# input5.net
KiCad netlist of a schematic drawn in Altium Designer
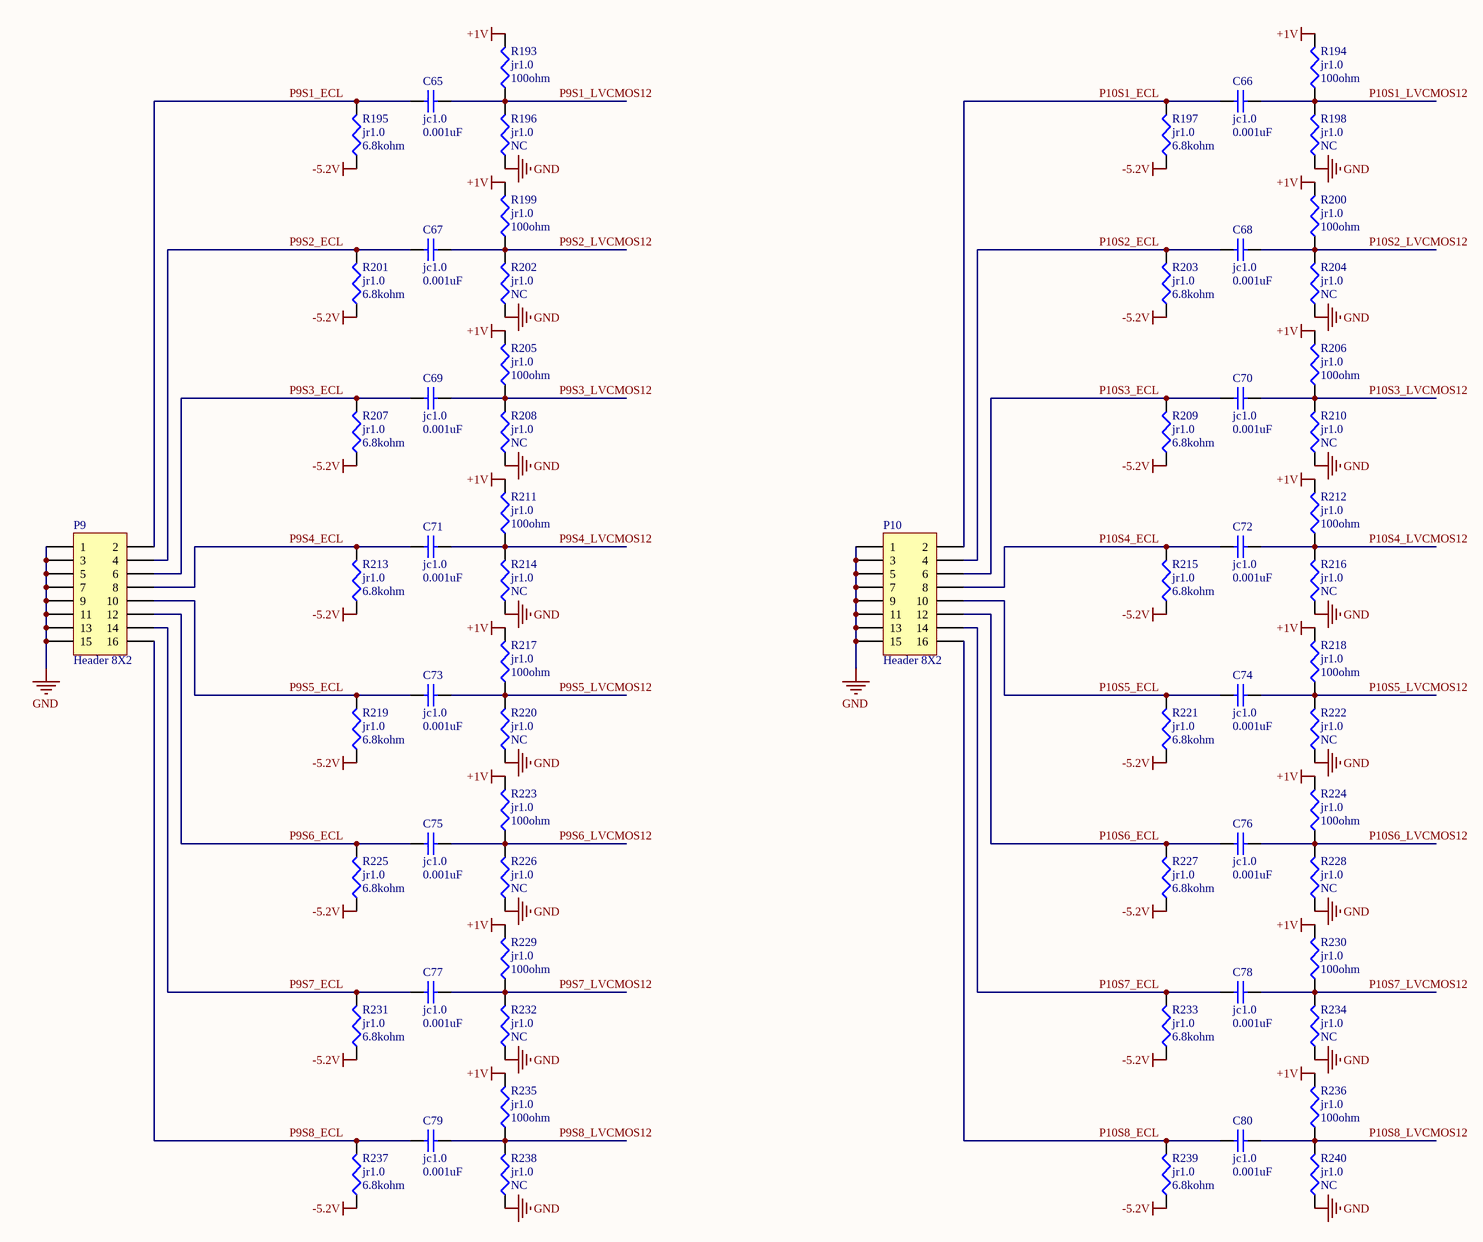
[diagram p0: input5.SchDoc]

(export (version "E")
  (design (tool "Eeschema 10.0.6"))
  (components
    (comp (ref "C65")
      (value "jc1.0")
      (footprint "0402")
      (description "Capacitor")
      (fields (field (name "ALTIUM_VALUE") "0.001uF") (field (name "PUBLISHER") "Altium Limited"))
      (libsource (lib "LIB01DXP2006SchLib") (part "Cap"))
    )
    (comp (ref "C66")
      (value "jc1.0")
      (footprint "0402")
      (description "Capacitor")
      (fields (field (name "ALTIUM_VALUE") "0.001uF") (field (name "PUBLISHER") "Altium Limited"))
      (libsource (lib "LIB01DXP2006SchLib") (part "Cap"))
    )
    (comp (ref "C67")
      (value "jc1.0")
      (footprint "0402")
      (description "Capacitor")
      (fields (field (name "ALTIUM_VALUE") "0.001uF") (field (name "PUBLISHER") "Altium Limited"))
      (libsource (lib "LIB01DXP2006SchLib") (part "Cap"))
    )
    (comp (ref "C68")
      (value "jc1.0")
      (footprint "0402")
      (description "Capacitor")
      (fields (field (name "ALTIUM_VALUE") "0.001uF") (field (name "PUBLISHER") "Altium Limited"))
      (libsource (lib "LIB01DXP2006SchLib") (part "Cap"))
    )
    (comp (ref "C69")
      (value "jc1.0")
      (footprint "0402")
      (description "Capacitor")
      (fields (field (name "ALTIUM_VALUE") "0.001uF") (field (name "PUBLISHER") "Altium Limited"))
      (libsource (lib "LIB01DXP2006SchLib") (part "Cap"))
    )
    (comp (ref "C70")
      (value "jc1.0")
      (footprint "0402")
      (description "Capacitor")
      (fields (field (name "ALTIUM_VALUE") "0.001uF") (field (name "PUBLISHER") "Altium Limited"))
      (libsource (lib "LIB01DXP2006SchLib") (part "Cap"))
    )
    (comp (ref "C71")
      (value "jc1.0")
      (footprint "0402")
      (description "Capacitor")
      (fields (field (name "ALTIUM_VALUE") "0.001uF") (field (name "PUBLISHER") "Altium Limited"))
      (libsource (lib "LIB01DXP2006SchLib") (part "Cap"))
    )
    (comp (ref "C72")
      (value "jc1.0")
      (footprint "0402")
      (description "Capacitor")
      (fields (field (name "ALTIUM_VALUE") "0.001uF") (field (name "PUBLISHER") "Altium Limited"))
      (libsource (lib "LIB01DXP2006SchLib") (part "Cap"))
    )
    (comp (ref "C73")
      (value "jc1.0")
      (footprint "0402")
      (description "Capacitor")
      (fields (field (name "ALTIUM_VALUE") "0.001uF") (field (name "PUBLISHER") "Altium Limited"))
      (libsource (lib "LIB01DXP2006SchLib") (part "Cap"))
    )
    (comp (ref "C74")
      (value "jc1.0")
      (footprint "0402")
      (description "Capacitor")
      (fields (field (name "ALTIUM_VALUE") "0.001uF") (field (name "PUBLISHER") "Altium Limited"))
      (libsource (lib "LIB01DXP2006SchLib") (part "Cap"))
    )
    (comp (ref "C75")
      (value "jc1.0")
      (footprint "0402")
      (description "Capacitor")
      (fields (field (name "ALTIUM_VALUE") "0.001uF") (field (name "PUBLISHER") "Altium Limited"))
      (libsource (lib "LIB01DXP2006SchLib") (part "Cap"))
    )
    (comp (ref "C76")
      (value "jc1.0")
      (footprint "0402")
      (description "Capacitor")
      (fields (field (name "ALTIUM_VALUE") "0.001uF") (field (name "PUBLISHER") "Altium Limited"))
      (libsource (lib "LIB01DXP2006SchLib") (part "Cap"))
    )
    (comp (ref "C77")
      (value "jc1.0")
      (footprint "0402")
      (description "Capacitor")
      (fields (field (name "ALTIUM_VALUE") "0.001uF") (field (name "PUBLISHER") "Altium Limited"))
      (libsource (lib "LIB01DXP2006SchLib") (part "Cap"))
    )
    (comp (ref "C78")
      (value "jc1.0")
      (footprint "0402")
      (description "Capacitor")
      (fields (field (name "ALTIUM_VALUE") "0.001uF") (field (name "PUBLISHER") "Altium Limited"))
      (libsource (lib "LIB01DXP2006SchLib") (part "Cap"))
    )
    (comp (ref "C79")
      (value "jc1.0")
      (footprint "0402")
      (description "Capacitor")
      (fields (field (name "ALTIUM_VALUE") "0.001uF") (field (name "PUBLISHER") "Altium Limited"))
      (libsource (lib "LIB01DXP2006SchLib") (part "Cap"))
    )
    (comp (ref "C80")
      (value "jc1.0")
      (footprint "0402")
      (description "Capacitor")
      (fields (field (name "ALTIUM_VALUE") "0.001uF") (field (name "PUBLISHER") "Altium Limited"))
      (libsource (lib "LIB01DXP2006SchLib") (part "Cap"))
    )
    (comp (ref "P9")
      (value "Header 8X2")
      (footprint "HDR2X8")
      (description "Header, 8-Pin, Dual row")
      (fields (field (name "PUBLISHER") "Altium Limited"))
      (libsource (lib "Miscellaneous Connectors") (part "Header 8X2"))
    )
    (comp (ref "P10")
      (value "Header 8X2")
      (footprint "HDR2X8")
      (description "Header, 8-Pin, Dual row")
      (fields (field (name "PUBLISHER") "Altium Limited"))
      (libsource (lib "Miscellaneous Connectors") (part "Header 8X2"))
    )
    (comp (ref "R193")
      (value "jr1.0")
      (footprint "0402")
      (description "Resistor")
      (fields (field (name "ALTIUM_VALUE") "100ohm") (field (name "PUBLISHER") "Altium Limited"))
      (libsource (lib "LIB01DXP2006SchLib") (part "Res"))
    )
    (comp (ref "R194")
      (value "jr1.0")
      (footprint "0402")
      (description "Resistor")
      (fields (field (name "ALTIUM_VALUE") "100ohm") (field (name "PUBLISHER") "Altium Limited"))
      (libsource (lib "LIB01DXP2006SchLib") (part "Res"))
    )
    (comp (ref "R195")
      (value "jr1.0")
      (footprint "0402")
      (description "Resistor")
      (fields (field (name "ALTIUM_VALUE") "6.8kohm") (field (name "PUBLISHER") "Altium Limited"))
      (libsource (lib "LIB01DXP2006SchLib") (part "Res"))
    )
    (comp (ref "R196")
      (value "jr1.0")
      (footprint "0402")
      (description "Resistor")
      (fields (field (name "ALTIUM_VALUE") "NC") (field (name "PUBLISHER") "Altium Limited"))
      (libsource (lib "LIB01DXP2006SchLib") (part "Res"))
    )
    (comp (ref "R197")
      (value "jr1.0")
      (footprint "0402")
      (description "Resistor")
      (fields (field (name "ALTIUM_VALUE") "6.8kohm") (field (name "PUBLISHER") "Altium Limited"))
      (libsource (lib "LIB01DXP2006SchLib") (part "Res"))
    )
    (comp (ref "R198")
      (value "jr1.0")
      (footprint "0402")
      (description "Resistor")
      (fields (field (name "ALTIUM_VALUE") "NC") (field (name "PUBLISHER") "Altium Limited"))
      (libsource (lib "LIB01DXP2006SchLib") (part "Res"))
    )
    (comp (ref "R199")
      (value "jr1.0")
      (footprint "0402")
      (description "Resistor")
      (fields (field (name "ALTIUM_VALUE") "100ohm") (field (name "PUBLISHER") "Altium Limited"))
      (libsource (lib "LIB01DXP2006SchLib") (part "Res"))
    )
    (comp (ref "R200")
      (value "jr1.0")
      (footprint "0402")
      (description "Resistor")
      (fields (field (name "ALTIUM_VALUE") "100ohm") (field (name "PUBLISHER") "Altium Limited"))
      (libsource (lib "LIB01DXP2006SchLib") (part "Res"))
    )
    (comp (ref "R201")
      (value "jr1.0")
      (footprint "0402")
      (description "Resistor")
      (fields (field (name "ALTIUM_VALUE") "6.8kohm") (field (name "PUBLISHER") "Altium Limited"))
      (libsource (lib "LIB01DXP2006SchLib") (part "Res"))
    )
    (comp (ref "R202")
      (value "jr1.0")
      (footprint "0402")
      (description "Resistor")
      (fields (field (name "ALTIUM_VALUE") "NC") (field (name "PUBLISHER") "Altium Limited"))
      (libsource (lib "LIB01DXP2006SchLib") (part "Res"))
    )
    (comp (ref "R203")
      (value "jr1.0")
      (footprint "0402")
      (description "Resistor")
      (fields (field (name "ALTIUM_VALUE") "6.8kohm") (field (name "PUBLISHER") "Altium Limited"))
      (libsource (lib "LIB01DXP2006SchLib") (part "Res"))
    )
    (comp (ref "R204")
      (value "jr1.0")
      (footprint "0402")
      (description "Resistor")
      (fields (field (name "ALTIUM_VALUE") "NC") (field (name "PUBLISHER") "Altium Limited"))
      (libsource (lib "LIB01DXP2006SchLib") (part "Res"))
    )
    (comp (ref "R205")
      (value "jr1.0")
      (footprint "0402")
      (description "Resistor")
      (fields (field (name "ALTIUM_VALUE") "100ohm") (field (name "PUBLISHER") "Altium Limited"))
      (libsource (lib "LIB01DXP2006SchLib") (part "Res"))
    )
    (comp (ref "R206")
      (value "jr1.0")
      (footprint "0402")
      (description "Resistor")
      (fields (field (name "ALTIUM_VALUE") "100ohm") (field (name "PUBLISHER") "Altium Limited"))
      (libsource (lib "LIB01DXP2006SchLib") (part "Res"))
    )
    (comp (ref "R207")
      (value "jr1.0")
      (footprint "0402")
      (description "Resistor")
      (fields (field (name "ALTIUM_VALUE") "6.8kohm") (field (name "PUBLISHER") "Altium Limited"))
      (libsource (lib "LIB01DXP2006SchLib") (part "Res"))
    )
    (comp (ref "R208")
      (value "jr1.0")
      (footprint "0402")
      (description "Resistor")
      (fields (field (name "ALTIUM_VALUE") "NC") (field (name "PUBLISHER") "Altium Limited"))
      (libsource (lib "LIB01DXP2006SchLib") (part "Res"))
    )
    (comp (ref "R209")
      (value "jr1.0")
      (footprint "0402")
      (description "Resistor")
      (fields (field (name "ALTIUM_VALUE") "6.8kohm") (field (name "PUBLISHER") "Altium Limited"))
      (libsource (lib "LIB01DXP2006SchLib") (part "Res"))
    )
    (comp (ref "R210")
      (value "jr1.0")
      (footprint "0402")
      (description "Resistor")
      (fields (field (name "ALTIUM_VALUE") "NC") (field (name "PUBLISHER") "Altium Limited"))
      (libsource (lib "LIB01DXP2006SchLib") (part "Res"))
    )
    (comp (ref "R211")
      (value "jr1.0")
      (footprint "0402")
      (description "Resistor")
      (fields (field (name "ALTIUM_VALUE") "100ohm") (field (name "PUBLISHER") "Altium Limited"))
      (libsource (lib "LIB01DXP2006SchLib") (part "Res"))
    )
    (comp (ref "R212")
      (value "jr1.0")
      (footprint "0402")
      (description "Resistor")
      (fields (field (name "ALTIUM_VALUE") "100ohm") (field (name "PUBLISHER") "Altium Limited"))
      (libsource (lib "LIB01DXP2006SchLib") (part "Res"))
    )
    (comp (ref "R213")
      (value "jr1.0")
      (footprint "0402")
      (description "Resistor")
      (fields (field (name "ALTIUM_VALUE") "6.8kohm") (field (name "PUBLISHER") "Altium Limited"))
      (libsource (lib "LIB01DXP2006SchLib") (part "Res"))
    )
    (comp (ref "R214")
      (value "jr1.0")
      (footprint "0402")
      (description "Resistor")
      (fields (field (name "ALTIUM_VALUE") "NC") (field (name "PUBLISHER") "Altium Limited"))
      (libsource (lib "LIB01DXP2006SchLib") (part "Res"))
    )
    (comp (ref "R215")
      (value "jr1.0")
      (footprint "0402")
      (description "Resistor")
      (fields (field (name "ALTIUM_VALUE") "6.8kohm") (field (name "PUBLISHER") "Altium Limited"))
      (libsource (lib "LIB01DXP2006SchLib") (part "Res"))
    )
    (comp (ref "R216")
      (value "jr1.0")
      (footprint "0402")
      (description "Resistor")
      (fields (field (name "ALTIUM_VALUE") "NC") (field (name "PUBLISHER") "Altium Limited"))
      (libsource (lib "LIB01DXP2006SchLib") (part "Res"))
    )
    (comp (ref "R217")
      (value "jr1.0")
      (footprint "0402")
      (description "Resistor")
      (fields (field (name "ALTIUM_VALUE") "100ohm") (field (name "PUBLISHER") "Altium Limited"))
      (libsource (lib "LIB01DXP2006SchLib") (part "Res"))
    )
    (comp (ref "R218")
      (value "jr1.0")
      (footprint "0402")
      (description "Resistor")
      (fields (field (name "ALTIUM_VALUE") "100ohm") (field (name "PUBLISHER") "Altium Limited"))
      (libsource (lib "LIB01DXP2006SchLib") (part "Res"))
    )
    (comp (ref "R219")
      (value "jr1.0")
      (footprint "0402")
      (description "Resistor")
      (fields (field (name "ALTIUM_VALUE") "6.8kohm") (field (name "PUBLISHER") "Altium Limited"))
      (libsource (lib "LIB01DXP2006SchLib") (part "Res"))
    )
    (comp (ref "R220")
      (value "jr1.0")
      (footprint "0402")
      (description "Resistor")
      (fields (field (name "ALTIUM_VALUE") "NC") (field (name "PUBLISHER") "Altium Limited"))
      (libsource (lib "LIB01DXP2006SchLib") (part "Res"))
    )
    (comp (ref "R221")
      (value "jr1.0")
      (footprint "0402")
      (description "Resistor")
      (fields (field (name "ALTIUM_VALUE") "6.8kohm") (field (name "PUBLISHER") "Altium Limited"))
      (libsource (lib "LIB01DXP2006SchLib") (part "Res"))
    )
    (comp (ref "R222")
      (value "jr1.0")
      (footprint "0402")
      (description "Resistor")
      (fields (field (name "ALTIUM_VALUE") "NC") (field (name "PUBLISHER") "Altium Limited"))
      (libsource (lib "LIB01DXP2006SchLib") (part "Res"))
    )
    (comp (ref "R223")
      (value "jr1.0")
      (footprint "0402")
      (description "Resistor")
      (fields (field (name "ALTIUM_VALUE") "100ohm") (field (name "PUBLISHER") "Altium Limited"))
      (libsource (lib "LIB01DXP2006SchLib") (part "Res"))
    )
    (comp (ref "R224")
      (value "jr1.0")
      (footprint "0402")
      (description "Resistor")
      (fields (field (name "ALTIUM_VALUE") "100ohm") (field (name "PUBLISHER") "Altium Limited"))
      (libsource (lib "LIB01DXP2006SchLib") (part "Res"))
    )
    (comp (ref "R225")
      (value "jr1.0")
      (footprint "0402")
      (description "Resistor")
      (fields (field (name "ALTIUM_VALUE") "6.8kohm") (field (name "PUBLISHER") "Altium Limited"))
      (libsource (lib "LIB01DXP2006SchLib") (part "Res"))
    )
    (comp (ref "R226")
      (value "jr1.0")
      (footprint "0402")
      (description "Resistor")
      (fields (field (name "ALTIUM_VALUE") "NC") (field (name "PUBLISHER") "Altium Limited"))
      (libsource (lib "LIB01DXP2006SchLib") (part "Res"))
    )
    (comp (ref "R227")
      (value "jr1.0")
      (footprint "0402")
      (description "Resistor")
      (fields (field (name "ALTIUM_VALUE") "6.8kohm") (field (name "PUBLISHER") "Altium Limited"))
      (libsource (lib "LIB01DXP2006SchLib") (part "Res"))
    )
    (comp (ref "R228")
      (value "jr1.0")
      (footprint "0402")
      (description "Resistor")
      (fields (field (name "ALTIUM_VALUE") "NC") (field (name "PUBLISHER") "Altium Limited"))
      (libsource (lib "LIB01DXP2006SchLib") (part "Res"))
    )
    (comp (ref "R229")
      (value "jr1.0")
      (footprint "0402")
      (description "Resistor")
      (fields (field (name "ALTIUM_VALUE") "100ohm") (field (name "PUBLISHER") "Altium Limited"))
      (libsource (lib "LIB01DXP2006SchLib") (part "Res"))
    )
    (comp (ref "R230")
      (value "jr1.0")
      (footprint "0402")
      (description "Resistor")
      (fields (field (name "ALTIUM_VALUE") "100ohm") (field (name "PUBLISHER") "Altium Limited"))
      (libsource (lib "LIB01DXP2006SchLib") (part "Res"))
    )
    (comp (ref "R231")
      (value "jr1.0")
      (footprint "0402")
      (description "Resistor")
      (fields (field (name "ALTIUM_VALUE") "6.8kohm") (field (name "PUBLISHER") "Altium Limited"))
      (libsource (lib "LIB01DXP2006SchLib") (part "Res"))
    )
    (comp (ref "R232")
      (value "jr1.0")
      (footprint "0402")
      (description "Resistor")
      (fields (field (name "ALTIUM_VALUE") "NC") (field (name "PUBLISHER") "Altium Limited"))
      (libsource (lib "LIB01DXP2006SchLib") (part "Res"))
    )
    (comp (ref "R233")
      (value "jr1.0")
      (footprint "0402")
      (description "Resistor")
      (fields (field (name "ALTIUM_VALUE") "6.8kohm") (field (name "PUBLISHER") "Altium Limited"))
      (libsource (lib "LIB01DXP2006SchLib") (part "Res"))
    )
    (comp (ref "R234")
      (value "jr1.0")
      (footprint "0402")
      (description "Resistor")
      (fields (field (name "ALTIUM_VALUE") "NC") (field (name "PUBLISHER") "Altium Limited"))
      (libsource (lib "LIB01DXP2006SchLib") (part "Res"))
    )
    (comp (ref "R235")
      (value "jr1.0")
      (footprint "0402")
      (description "Resistor")
      (fields (field (name "ALTIUM_VALUE") "100ohm") (field (name "PUBLISHER") "Altium Limited"))
      (libsource (lib "LIB01DXP2006SchLib") (part "Res"))
    )
    (comp (ref "R236")
      (value "jr1.0")
      (footprint "0402")
      (description "Resistor")
      (fields (field (name "ALTIUM_VALUE") "100ohm") (field (name "PUBLISHER") "Altium Limited"))
      (libsource (lib "LIB01DXP2006SchLib") (part "Res"))
    )
    (comp (ref "R237")
      (value "jr1.0")
      (footprint "0402")
      (description "Resistor")
      (fields (field (name "ALTIUM_VALUE") "6.8kohm") (field (name "PUBLISHER") "Altium Limited"))
      (libsource (lib "LIB01DXP2006SchLib") (part "Res"))
    )
    (comp (ref "R238")
      (value "jr1.0")
      (footprint "0402")
      (description "Resistor")
      (fields (field (name "ALTIUM_VALUE") "NC") (field (name "PUBLISHER") "Altium Limited"))
      (libsource (lib "LIB01DXP2006SchLib") (part "Res"))
    )
    (comp (ref "R239")
      (value "jr1.0")
      (footprint "0402")
      (description "Resistor")
      (fields (field (name "ALTIUM_VALUE") "6.8kohm") (field (name "PUBLISHER") "Altium Limited"))
      (libsource (lib "LIB01DXP2006SchLib") (part "Res"))
    )
    (comp (ref "R240")
      (value "jr1.0")
      (footprint "0402")
      (description "Resistor")
      (fields (field (name "ALTIUM_VALUE") "NC") (field (name "PUBLISHER") "Altium Limited"))
      (libsource (lib "LIB01DXP2006SchLib") (part "Res"))
    )
  )
  (nets
    (net (code "1") (name "+1V") (class "Default")
      (node (ref "R193") (pin "2") (pinfunction "2_2") (pintype "passive"))
      (node (ref "R194") (pin "2") (pinfunction "2_2") (pintype "passive"))
      (node (ref "R199") (pin "2") (pinfunction "2_2") (pintype "passive"))
      (node (ref "R200") (pin "2") (pinfunction "2_2") (pintype "passive"))
      (node (ref "R205") (pin "2") (pinfunction "2_2") (pintype "passive"))
      (node (ref "R206") (pin "2") (pinfunction "2_2") (pintype "passive"))
      (node (ref "R211") (pin "2") (pinfunction "2_2") (pintype "passive"))
      (node (ref "R212") (pin "2") (pinfunction "2_2") (pintype "passive"))
      (node (ref "R217") (pin "2") (pinfunction "2_2") (pintype "passive"))
      (node (ref "R218") (pin "2") (pinfunction "2_2") (pintype "passive"))
      (node (ref "R223") (pin "2") (pinfunction "2_2") (pintype "passive"))
      (node (ref "R224") (pin "2") (pinfunction "2_2") (pintype "passive"))
      (node (ref "R229") (pin "2") (pinfunction "2_2") (pintype "passive"))
      (node (ref "R230") (pin "2") (pinfunction "2_2") (pintype "passive"))
      (node (ref "R235") (pin "2") (pinfunction "2_2") (pintype "passive"))
      (node (ref "R236") (pin "2") (pinfunction "2_2") (pintype "passive"))
    )
    (net (code "2") (name "-5.2V") (class "Default")
      (node (ref "R195") (pin "1") (pinfunction "1_1") (pintype "passive"))
      (node (ref "R197") (pin "1") (pinfunction "1_1") (pintype "passive"))
      (node (ref "R201") (pin "1") (pinfunction "1_1") (pintype "passive"))
      (node (ref "R203") (pin "1") (pinfunction "1_1") (pintype "passive"))
      (node (ref "R207") (pin "1") (pinfunction "1_1") (pintype "passive"))
      (node (ref "R209") (pin "1") (pinfunction "1_1") (pintype "passive"))
      (node (ref "R213") (pin "1") (pinfunction "1_1") (pintype "passive"))
      (node (ref "R215") (pin "1") (pinfunction "1_1") (pintype "passive"))
      (node (ref "R219") (pin "1") (pinfunction "1_1") (pintype "passive"))
      (node (ref "R221") (pin "1") (pinfunction "1_1") (pintype "passive"))
      (node (ref "R225") (pin "1") (pinfunction "1_1") (pintype "passive"))
      (node (ref "R227") (pin "1") (pinfunction "1_1") (pintype "passive"))
      (node (ref "R231") (pin "1") (pinfunction "1_1") (pintype "passive"))
      (node (ref "R233") (pin "1") (pinfunction "1_1") (pintype "passive"))
      (node (ref "R237") (pin "1") (pinfunction "1_1") (pintype "passive"))
      (node (ref "R239") (pin "1") (pinfunction "1_1") (pintype "passive"))
    )
    (net (code "3") (name "/P9S1_ECL") (class "Default")
      (node (ref "C65") (pin "1") (pinfunction "1_1") (pintype "passive"))
      (node (ref "P9") (pin "2") (pinfunction "2_2") (pintype "passive"))
      (node (ref "R195") (pin "2") (pinfunction "2_2") (pintype "passive"))
    )
    (net (code "4") (name "/P9S1_LVCMOS12") (class "Default")
      (node (ref "C65") (pin "2") (pinfunction "2_2") (pintype "passive"))
      (node (ref "R193") (pin "1") (pinfunction "1_1") (pintype "passive"))
      (node (ref "R196") (pin "2") (pinfunction "2_2") (pintype "passive"))
    )
    (net (code "5") (name "/P9S2_ECL") (class "Default")
      (node (ref "C67") (pin "1") (pinfunction "1_1") (pintype "passive"))
      (node (ref "P9") (pin "4") (pinfunction "4_4") (pintype "passive"))
      (node (ref "R201") (pin "2") (pinfunction "2_2") (pintype "passive"))
    )
    (net (code "6") (name "/P9S2_LVCMOS12") (class "Default")
      (node (ref "C67") (pin "2") (pinfunction "2_2") (pintype "passive"))
      (node (ref "R199") (pin "1") (pinfunction "1_1") (pintype "passive"))
      (node (ref "R202") (pin "2") (pinfunction "2_2") (pintype "passive"))
    )
    (net (code "7") (name "/P9S3_ECL") (class "Default")
      (node (ref "C69") (pin "1") (pinfunction "1_1") (pintype "passive"))
      (node (ref "P9") (pin "6") (pinfunction "6_6") (pintype "passive"))
      (node (ref "R207") (pin "2") (pinfunction "2_2") (pintype "passive"))
    )
    (net (code "8") (name "/P9S3_LVCMOS12") (class "Default")
      (node (ref "C69") (pin "2") (pinfunction "2_2") (pintype "passive"))
      (node (ref "R205") (pin "1") (pinfunction "1_1") (pintype "passive"))
      (node (ref "R208") (pin "2") (pinfunction "2_2") (pintype "passive"))
    )
    (net (code "9") (name "/P9S4_ECL") (class "Default")
      (node (ref "C71") (pin "1") (pinfunction "1_1") (pintype "passive"))
      (node (ref "P9") (pin "8") (pinfunction "8_8") (pintype "passive"))
      (node (ref "R213") (pin "2") (pinfunction "2_2") (pintype "passive"))
    )
    (net (code "10") (name "/P9S4_LVCMOS12") (class "Default")
      (node (ref "C71") (pin "2") (pinfunction "2_2") (pintype "passive"))
      (node (ref "R211") (pin "1") (pinfunction "1_1") (pintype "passive"))
      (node (ref "R214") (pin "2") (pinfunction "2_2") (pintype "passive"))
    )
    (net (code "11") (name "/P9S5_ECL") (class "Default")
      (node (ref "C73") (pin "1") (pinfunction "1_1") (pintype "passive"))
      (node (ref "P9") (pin "10") (pinfunction "10_10") (pintype "passive"))
      (node (ref "R219") (pin "2") (pinfunction "2_2") (pintype "passive"))
    )
    (net (code "12") (name "/P9S5_LVCMOS12") (class "Default")
      (node (ref "C73") (pin "2") (pinfunction "2_2") (pintype "passive"))
      (node (ref "R217") (pin "1") (pinfunction "1_1") (pintype "passive"))
      (node (ref "R220") (pin "2") (pinfunction "2_2") (pintype "passive"))
    )
    (net (code "13") (name "/P9S6_ECL") (class "Default")
      (node (ref "C75") (pin "1") (pinfunction "1_1") (pintype "passive"))
      (node (ref "P9") (pin "12") (pinfunction "12_12") (pintype "passive"))
      (node (ref "R225") (pin "2") (pinfunction "2_2") (pintype "passive"))
    )
    (net (code "14") (name "/P9S6_LVCMOS12") (class "Default")
      (node (ref "C75") (pin "2") (pinfunction "2_2") (pintype "passive"))
      (node (ref "R223") (pin "1") (pinfunction "1_1") (pintype "passive"))
      (node (ref "R226") (pin "2") (pinfunction "2_2") (pintype "passive"))
    )
    (net (code "15") (name "/P9S7_ECL") (class "Default")
      (node (ref "C77") (pin "1") (pinfunction "1_1") (pintype "passive"))
      (node (ref "P9") (pin "14") (pinfunction "14_14") (pintype "passive"))
      (node (ref "R231") (pin "2") (pinfunction "2_2") (pintype "passive"))
    )
    (net (code "16") (name "/P9S7_LVCMOS12") (class "Default")
      (node (ref "C77") (pin "2") (pinfunction "2_2") (pintype "passive"))
      (node (ref "R229") (pin "1") (pinfunction "1_1") (pintype "passive"))
      (node (ref "R232") (pin "2") (pinfunction "2_2") (pintype "passive"))
    )
    (net (code "17") (name "/P9S8_ECL") (class "Default")
      (node (ref "C79") (pin "1") (pinfunction "1_1") (pintype "passive"))
      (node (ref "P9") (pin "16") (pinfunction "16_16") (pintype "passive"))
      (node (ref "R237") (pin "2") (pinfunction "2_2") (pintype "passive"))
    )
    (net (code "18") (name "/P9S8_LVCMOS12") (class "Default")
      (node (ref "C79") (pin "2") (pinfunction "2_2") (pintype "passive"))
      (node (ref "R235") (pin "1") (pinfunction "1_1") (pintype "passive"))
      (node (ref "R238") (pin "2") (pinfunction "2_2") (pintype "passive"))
    )
    (net (code "19") (name "/P10S1_ECL") (class "Default")
      (node (ref "C66") (pin "1") (pinfunction "1_1") (pintype "passive"))
      (node (ref "P10") (pin "2") (pinfunction "2_2") (pintype "passive"))
      (node (ref "R197") (pin "2") (pinfunction "2_2") (pintype "passive"))
    )
    (net (code "20") (name "/P10S1_LVCMOS12") (class "Default")
      (node (ref "C66") (pin "2") (pinfunction "2_2") (pintype "passive"))
      (node (ref "R194") (pin "1") (pinfunction "1_1") (pintype "passive"))
      (node (ref "R198") (pin "2") (pinfunction "2_2") (pintype "passive"))
    )
    (net (code "21") (name "/P10S2_ECL") (class "Default")
      (node (ref "C68") (pin "1") (pinfunction "1_1") (pintype "passive"))
      (node (ref "P10") (pin "4") (pinfunction "4_4") (pintype "passive"))
      (node (ref "R203") (pin "2") (pinfunction "2_2") (pintype "passive"))
    )
    (net (code "22") (name "/P10S2_LVCMOS12") (class "Default")
      (node (ref "C68") (pin "2") (pinfunction "2_2") (pintype "passive"))
      (node (ref "R200") (pin "1") (pinfunction "1_1") (pintype "passive"))
      (node (ref "R204") (pin "2") (pinfunction "2_2") (pintype "passive"))
    )
    (net (code "23") (name "/P10S3_ECL") (class "Default")
      (node (ref "C70") (pin "1") (pinfunction "1_1") (pintype "passive"))
      (node (ref "P10") (pin "6") (pinfunction "6_6") (pintype "passive"))
      (node (ref "R209") (pin "2") (pinfunction "2_2") (pintype "passive"))
    )
    (net (code "24") (name "/P10S3_LVCMOS12") (class "Default")
      (node (ref "C70") (pin "2") (pinfunction "2_2") (pintype "passive"))
      (node (ref "R206") (pin "1") (pinfunction "1_1") (pintype "passive"))
      (node (ref "R210") (pin "2") (pinfunction "2_2") (pintype "passive"))
    )
    (net (code "25") (name "/P10S4_ECL") (class "Default")
      (node (ref "C72") (pin "1") (pinfunction "1_1") (pintype "passive"))
      (node (ref "P10") (pin "8") (pinfunction "8_8") (pintype "passive"))
      (node (ref "R215") (pin "2") (pinfunction "2_2") (pintype "passive"))
    )
    (net (code "26") (name "/P10S4_LVCMOS12") (class "Default")
      (node (ref "C72") (pin "2") (pinfunction "2_2") (pintype "passive"))
      (node (ref "R212") (pin "1") (pinfunction "1_1") (pintype "passive"))
      (node (ref "R216") (pin "2") (pinfunction "2_2") (pintype "passive"))
    )
    (net (code "27") (name "/P10S5_ECL") (class "Default")
      (node (ref "C74") (pin "1") (pinfunction "1_1") (pintype "passive"))
      (node (ref "P10") (pin "10") (pinfunction "10_10") (pintype "passive"))
      (node (ref "R221") (pin "2") (pinfunction "2_2") (pintype "passive"))
    )
    (net (code "28") (name "/P10S5_LVCMOS12") (class "Default")
      (node (ref "C74") (pin "2") (pinfunction "2_2") (pintype "passive"))
      (node (ref "R218") (pin "1") (pinfunction "1_1") (pintype "passive"))
      (node (ref "R222") (pin "2") (pinfunction "2_2") (pintype "passive"))
    )
    (net (code "29") (name "/P10S6_ECL") (class "Default")
      (node (ref "C76") (pin "1") (pinfunction "1_1") (pintype "passive"))
      (node (ref "P10") (pin "12") (pinfunction "12_12") (pintype "passive"))
      (node (ref "R227") (pin "2") (pinfunction "2_2") (pintype "passive"))
    )
    (net (code "30") (name "/P10S6_LVCMOS12") (class "Default")
      (node (ref "C76") (pin "2") (pinfunction "2_2") (pintype "passive"))
      (node (ref "R224") (pin "1") (pinfunction "1_1") (pintype "passive"))
      (node (ref "R228") (pin "2") (pinfunction "2_2") (pintype "passive"))
    )
    (net (code "31") (name "/P10S7_ECL") (class "Default")
      (node (ref "C78") (pin "1") (pinfunction "1_1") (pintype "passive"))
      (node (ref "P10") (pin "14") (pinfunction "14_14") (pintype "passive"))
      (node (ref "R233") (pin "2") (pinfunction "2_2") (pintype "passive"))
    )
    (net (code "32") (name "/P10S7_LVCMOS12") (class "Default")
      (node (ref "C78") (pin "2") (pinfunction "2_2") (pintype "passive"))
      (node (ref "R230") (pin "1") (pinfunction "1_1") (pintype "passive"))
      (node (ref "R234") (pin "2") (pinfunction "2_2") (pintype "passive"))
    )
    (net (code "33") (name "/P10S8_ECL") (class "Default")
      (node (ref "C80") (pin "1") (pinfunction "1_1") (pintype "passive"))
      (node (ref "P10") (pin "16") (pinfunction "16_16") (pintype "passive"))
      (node (ref "R239") (pin "2") (pinfunction "2_2") (pintype "passive"))
    )
    (net (code "34") (name "/P10S8_LVCMOS12") (class "Default")
      (node (ref "C80") (pin "2") (pinfunction "2_2") (pintype "passive"))
      (node (ref "R236") (pin "1") (pinfunction "1_1") (pintype "passive"))
      (node (ref "R240") (pin "2") (pinfunction "2_2") (pintype "passive"))
    )
    (net (code "35") (name "GND") (class "Default")
      (node (ref "P10") (pin "1") (pinfunction "1_1") (pintype "passive"))
      (node (ref "P10") (pin "11") (pinfunction "11_11") (pintype "passive"))
      (node (ref "P10") (pin "13") (pinfunction "13_13") (pintype "passive"))
      (node (ref "P10") (pin "15") (pinfunction "15_15") (pintype "passive"))
      (node (ref "P10") (pin "3") (pinfunction "3_3") (pintype "passive"))
      (node (ref "P10") (pin "5") (pinfunction "5_5") (pintype "passive"))
      (node (ref "P10") (pin "7") (pinfunction "7_7") (pintype "passive"))
      (node (ref "P10") (pin "9") (pinfunction "9_9") (pintype "passive"))
      (node (ref "P9") (pin "1") (pinfunction "1_1") (pintype "passive"))
      (node (ref "P9") (pin "11") (pinfunction "11_11") (pintype "passive"))
      (node (ref "P9") (pin "13") (pinfunction "13_13") (pintype "passive"))
      (node (ref "P9") (pin "15") (pinfunction "15_15") (pintype "passive"))
      (node (ref "P9") (pin "3") (pinfunction "3_3") (pintype "passive"))
      (node (ref "P9") (pin "5") (pinfunction "5_5") (pintype "passive"))
      (node (ref "P9") (pin "7") (pinfunction "7_7") (pintype "passive"))
      (node (ref "P9") (pin "9") (pinfunction "9_9") (pintype "passive"))
      (node (ref "R196") (pin "1") (pinfunction "1_1") (pintype "passive"))
      (node (ref "R198") (pin "1") (pinfunction "1_1") (pintype "passive"))
      (node (ref "R202") (pin "1") (pinfunction "1_1") (pintype "passive"))
      (node (ref "R204") (pin "1") (pinfunction "1_1") (pintype "passive"))
      (node (ref "R208") (pin "1") (pinfunction "1_1") (pintype "passive"))
      (node (ref "R210") (pin "1") (pinfunction "1_1") (pintype "passive"))
      (node (ref "R214") (pin "1") (pinfunction "1_1") (pintype "passive"))
      (node (ref "R216") (pin "1") (pinfunction "1_1") (pintype "passive"))
      (node (ref "R220") (pin "1") (pinfunction "1_1") (pintype "passive"))
      (node (ref "R222") (pin "1") (pinfunction "1_1") (pintype "passive"))
      (node (ref "R226") (pin "1") (pinfunction "1_1") (pintype "passive"))
      (node (ref "R228") (pin "1") (pinfunction "1_1") (pintype "passive"))
      (node (ref "R232") (pin "1") (pinfunction "1_1") (pintype "passive"))
      (node (ref "R234") (pin "1") (pinfunction "1_1") (pintype "passive"))
      (node (ref "R238") (pin "1") (pinfunction "1_1") (pintype "passive"))
      (node (ref "R240") (pin "1") (pinfunction "1_1") (pintype "passive"))
    )
  )
)
